# arduino.net
KiCad netlist of a schematic drawn in EAGLE
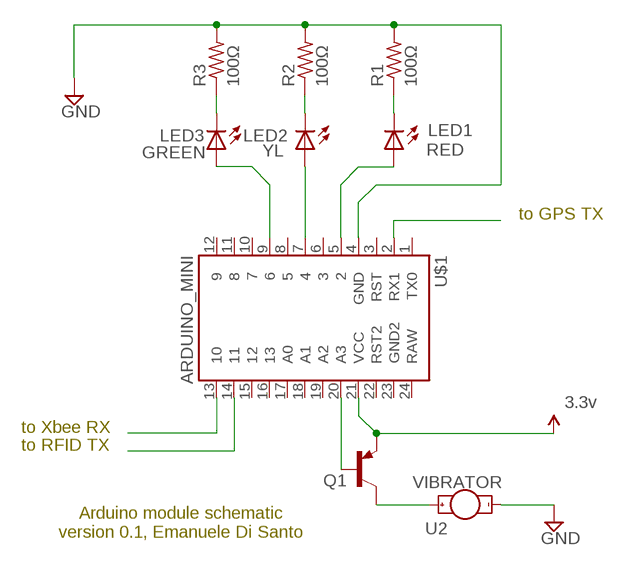
[diagram p0: schematic, sheet 1]

(export (version "E")
  (design (tool "Eeschema 10.0.6"))
  (components
    (comp (ref "LED1")
      (value "RED")
      (footprint "eagle-import:CHIPLED_0805")
      (libsource (lib "eagle-import") (part "LEDCHIPLED_0805"))
    )
    (comp (ref "LED2")
      (value "YL")
      (footprint "eagle-import:CHIPLED_0805")
      (libsource (lib "eagle-import") (part "LEDCHIPLED_0805"))
    )
    (comp (ref "LED3")
      (value "GREEN")
      (footprint "eagle-import:CHIPLED_0805")
      (libsource (lib "eagle-import") (part "LEDCHIPLED_0805"))
    )
    (comp (ref "Q1")
      (value "-PNP-TO92")
      (footprint "eagle-import:TO92")
      (libsource (lib "eagle-import") (part "-PNP-TO92"))
    )
    (comp (ref "R1")
      (value "100Ω")
      (footprint "eagle-import:R3216")
      (libsource (lib "eagle-import") (part "R-US_R3216"))
    )
    (comp (ref "R2")
      (value "100Ω")
      (footprint "eagle-import:R3216")
      (libsource (lib "eagle-import") (part "R-US_R3216"))
    )
    (comp (ref "R3")
      (value "100Ω")
      (footprint "eagle-import:R3216")
      (libsource (lib "eagle-import") (part "R-US_R3216"))
    )
    (comp (ref "U$1")
      (value "ARDUINO_MINI")
      (footprint "eagle-import:ARDUINO_MINI")
      (libsource (lib "eagle-import") (part "ARDUINO_MINI"))
    )
    (comp (ref "U2")
      (value "VIBRATOR")
      (footprint "eagle-import:VIBE-MOTOR-10MM")
      (libsource (lib "eagle-import") (part "MOTOR10MM"))
    )
  )
  (nets
    (net (code "1") (name "3.3v") (class "Default")
      (node (ref "Q1") (pin "1") (pinfunction "E_1") (pintype "passive"))
      (node (ref "U$1") (pin "21") (pinfunction "VCC_21") (pintype "bidirectional"))
    )
    (net (code "2") (name "GND") (class "Default")
      (node (ref "R1") (pin "2") (pinfunction "2_2") (pintype "passive"))
      (node (ref "R2") (pin "2") (pinfunction "2_2") (pintype "passive"))
      (node (ref "R3") (pin "2") (pinfunction "2_2") (pintype "passive"))
      (node (ref "U$1") (pin "4") (pinfunction "GND_4") (pintype "bidirectional"))
      (node (ref "U2") (pin "-") (pinfunction "-_-") (pintype "bidirectional"))
    )
    (net (code "3") (name "Net-(LED1-PadC)") (class "Default")
      (node (ref "LED1") (pin "C") (pinfunction "C_C") (pintype "passive"))
      (node (ref "R1") (pin "1") (pinfunction "1_1") (pintype "passive"))
    )
    (net (code "4") (name "Net-(LED2-PadC)") (class "Default")
      (node (ref "LED2") (pin "C") (pinfunction "C_C") (pintype "passive"))
      (node (ref "R2") (pin "1") (pinfunction "1_1") (pintype "passive"))
    )
    (net (code "5") (name "Net-(LED3-PadC)") (class "Default")
      (node (ref "LED3") (pin "C") (pinfunction "C_C") (pintype "passive"))
      (node (ref "R3") (pin "1") (pinfunction "1_1") (pintype "passive"))
    )
    (net (code "6") (name "Net-(Q1-B)") (class "Default")
      (node (ref "Q1") (pin "2") (pinfunction "B_2") (pintype "passive"))
      (node (ref "U$1") (pin "20") (pinfunction "A3_20") (pintype "bidirectional"))
    )
    (net (code "7") (name "Net-(Q1-C)") (class "Default")
      (node (ref "Q1") (pin "3") (pinfunction "C_3") (pintype "passive"))
      (node (ref "U2") (pin "+") (pinfunction "+_+") (pintype "bidirectional"))
    )
    (net (code "8") (name "Net-(U$1-2)") (class "Default")
      (node (ref "LED1") (pin "A") (pinfunction "A_A") (pintype "passive"))
      (node (ref "U$1") (pin "5") (pinfunction "2_5") (pintype "bidirectional"))
    )
    (net (code "9") (name "Net-(U$1-4)") (class "Default")
      (node (ref "LED2") (pin "A") (pinfunction "A_A") (pintype "passive"))
      (node (ref "U$1") (pin "7") (pinfunction "4_7") (pintype "bidirectional"))
    )
    (net (code "10") (name "Net-(U$1-6)") (class "Default")
      (node (ref "LED3") (pin "A") (pinfunction "A_A") (pintype "passive"))
      (node (ref "U$1") (pin "9") (pinfunction "6_9") (pintype "bidirectional"))
    )
    (net (code "11") (name "unconnected-(U$1-3-Pad6)") (class "Default")
      (node (ref "U$1") (pin "6") (pinfunction "3_6") (pintype "bidirectional"))
    )
    (net (code "12") (name "unconnected-(U$1-5-Pad8)") (class "Default")
      (node (ref "U$1") (pin "8") (pinfunction "5_8") (pintype "bidirectional"))
    )
    (net (code "13") (name "unconnected-(U$1-7-Pad10)") (class "Default")
      (node (ref "U$1") (pin "10") (pinfunction "7_10") (pintype "bidirectional"))
    )
    (net (code "14") (name "unconnected-(U$1-8-Pad11)") (class "Default")
      (node (ref "U$1") (pin "11") (pinfunction "8_11") (pintype "bidirectional"))
    )
    (net (code "15") (name "unconnected-(U$1-9-Pad12)") (class "Default")
      (node (ref "U$1") (pin "12") (pinfunction "9_12") (pintype "bidirectional"))
    )
    (net (code "16") (name "unconnected-(U$1-10-Pad13)") (class "Default")
      (node (ref "U$1") (pin "13") (pinfunction "10_13") (pintype "bidirectional"))
    )
    (net (code "17") (name "unconnected-(U$1-11-Pad14)") (class "Default")
      (node (ref "U$1") (pin "14") (pinfunction "11_14") (pintype "bidirectional"))
    )
    (net (code "18") (name "unconnected-(U$1-12-Pad15)") (class "Default")
      (node (ref "U$1") (pin "15") (pinfunction "12_15") (pintype "bidirectional"))
    )
    (net (code "19") (name "unconnected-(U$1-13-Pad16)") (class "Default")
      (node (ref "U$1") (pin "16") (pinfunction "13_16") (pintype "bidirectional"))
    )
    (net (code "20") (name "unconnected-(U$1-A0-Pad17)") (class "Default")
      (node (ref "U$1") (pin "17") (pinfunction "A0_17") (pintype "bidirectional"))
    )
    (net (code "21") (name "unconnected-(U$1-A1-Pad18)") (class "Default")
      (node (ref "U$1") (pin "18") (pinfunction "A1_18") (pintype "bidirectional"))
    )
    (net (code "22") (name "unconnected-(U$1-A2-Pad19)") (class "Default")
      (node (ref "U$1") (pin "19") (pinfunction "A2_19") (pintype "bidirectional"))
    )
    (net (code "23") (name "unconnected-(U$1-GND2-Pad23)") (class "Default")
      (node (ref "U$1") (pin "23") (pinfunction "GND2_23") (pintype "bidirectional"))
    )
    (net (code "24") (name "unconnected-(U$1-RAW-Pad24)") (class "Default")
      (node (ref "U$1") (pin "24") (pinfunction "RAW_24") (pintype "bidirectional"))
    )
    (net (code "25") (name "unconnected-(U$1-RST-Pad3)") (class "Default")
      (node (ref "U$1") (pin "3") (pinfunction "RST_3") (pintype "bidirectional"))
    )
    (net (code "26") (name "unconnected-(U$1-RST2-Pad22)") (class "Default")
      (node (ref "U$1") (pin "22") (pinfunction "RST2_22") (pintype "bidirectional"))
    )
    (net (code "27") (name "unconnected-(U$1-RX1-Pad2)") (class "Default")
      (node (ref "U$1") (pin "2") (pinfunction "RX1_2") (pintype "bidirectional"))
    )
    (net (code "28") (name "unconnected-(U$1-TX0-Pad1)") (class "Default")
      (node (ref "U$1") (pin "1") (pinfunction "TX0_1") (pintype "bidirectional"))
    )
  )
)
